# esquema_sensor.net
KiCad netlist of a schematic drawn in EAGLE
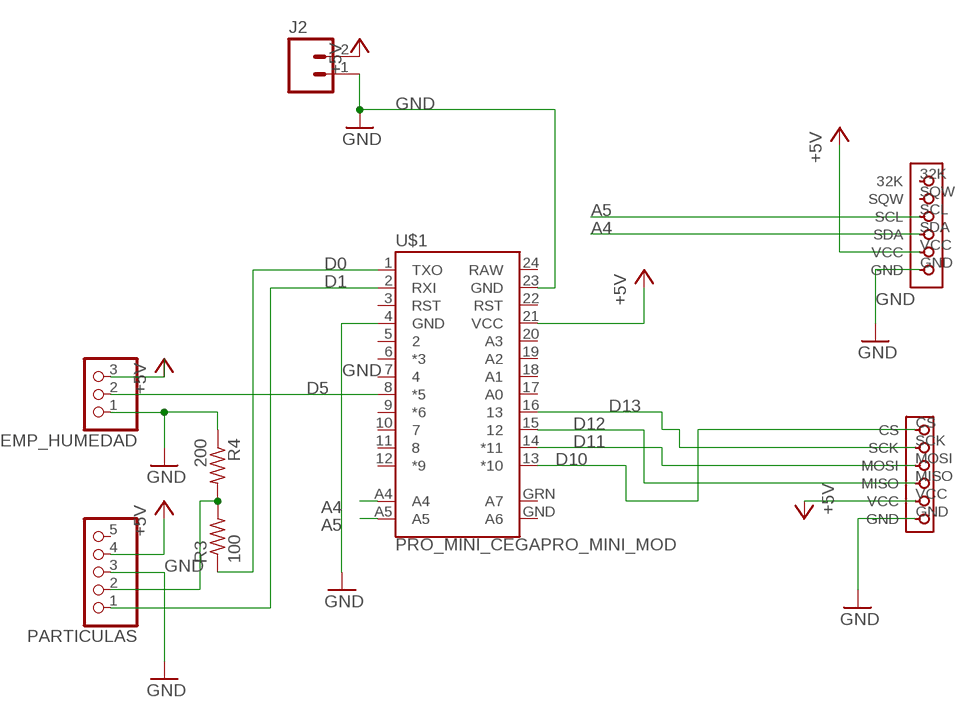
[diagram p0: schematic, sheet 1]

(export (version "E")
  (design (tool "Eeschema 10.0.6"))
  (components
    (comp (ref "J2")
      (value "M025MM")
      (footprint "eagle-import:SCREWTERMINAL-5MM-2")
      (libsource (lib "eagle-import") (part "M025MM"))
    )
    (comp (ref "PARTICULAS")
      (value "PINHD-1X5")
      (footprint "eagle-import:1X05")
      (libsource (lib "eagle-import") (part "PINHD-1X5"))
    )
    (comp (ref "R3")
      (value "100")
      (footprint "eagle-import:0207_7")
      (libsource (lib "eagle-import") (part "R-US_0207/7"))
    )
    (comp (ref "R4")
      (value "200")
      (footprint "eagle-import:0207_7")
      (libsource (lib "eagle-import") (part "R-US_0207/7"))
    )
    (comp (ref "RTC")
      (value "DS3231_RTC")
      (footprint "eagle-import:DS3231_RTC")
      (libsource (lib "eagle-import") (part "DS3231_RTC"))
    )
    (comp (ref "SD_READER")
      (value "MICRO_SD_READER")
      (footprint "eagle-import:MICRO_SD_READER")
      (libsource (lib "eagle-import") (part "MICRO_SD_READER"))
    )
    (comp (ref "TEMP_HUMEDAD")
      (value "PINHD-1X3")
      (footprint "eagle-import:1X03")
      (libsource (lib "eagle-import") (part "PINHD-1X3"))
    )
    (comp (ref "U$1")
      (value "PRO_MINI_CEGAPRO_MINI_MOD")
      (footprint "eagle-import:ARDUINO_PRO_MINI_MOD")
      (libsource (lib "eagle-import") (part "PRO_MINI_CEGAPRO_MINI_MOD"))
    )
  )
  (nets
    (net (code "1") (name "+5V") (class "Default")
      (node (ref "J2") (pin "2") (pinfunction "2_2") (pintype "passive"))
      (node (ref "PARTICULAS") (pin "4") (pinfunction "4_4") (pintype "passive"))
      (node (ref "RTC") (pin "VCC") (pinfunction "VCC_VCC") (pintype "bidirectional"))
      (node (ref "SD_READER") (pin "VCC") (pinfunction "VCC_VCC") (pintype "bidirectional"))
      (node (ref "TEMP_HUMEDAD") (pin "3") (pinfunction "3_3") (pintype "passive"))
      (node (ref "U$1") (pin "21") (pinfunction "VCC_21") (pintype "power_in"))
    )
    (net (code "2") (name "/A4") (class "Default")
      (node (ref "RTC") (pin "SDA") (pinfunction "SDA_SDA") (pintype "bidirectional"))
      (node (ref "U$1") (pin "A4") (pinfunction "A4_A4") (pintype "bidirectional"))
    )
    (net (code "3") (name "/A5") (class "Default")
      (node (ref "RTC") (pin "SCL") (pinfunction "SCL_SCL") (pintype "bidirectional"))
      (node (ref "U$1") (pin "A5") (pinfunction "A5_A5") (pintype "bidirectional"))
    )
    (net (code "4") (name "/D0") (class "Default")
      (node (ref "R3") (pin "1") (pinfunction "1_1") (pintype "passive"))
      (node (ref "U$1") (pin "1") (pinfunction "TXO_1") (pintype "bidirectional"))
    )
    (net (code "5") (name "/D1") (class "Default")
      (node (ref "PARTICULAS") (pin "1") (pinfunction "1_1") (pintype "passive"))
      (node (ref "U$1") (pin "2") (pinfunction "RXI_2") (pintype "bidirectional"))
    )
    (net (code "6") (name "/D5") (class "Default")
      (node (ref "TEMP_HUMEDAD") (pin "2") (pinfunction "2_2") (pintype "passive"))
      (node (ref "U$1") (pin "8") (pinfunction "*5_8") (pintype "bidirectional"))
    )
    (net (code "7") (name "/D10") (class "Default")
      (node (ref "SD_READER") (pin "CS") (pinfunction "CS_CS") (pintype "bidirectional"))
      (node (ref "U$1") (pin "13") (pinfunction "*10_13") (pintype "bidirectional"))
    )
    (net (code "8") (name "/D11") (class "Default")
      (node (ref "SD_READER") (pin "MOSI") (pinfunction "MOSI_MOSI") (pintype "bidirectional"))
      (node (ref "U$1") (pin "14") (pinfunction "*11_14") (pintype "bidirectional"))
    )
    (net (code "9") (name "/D12") (class "Default")
      (node (ref "SD_READER") (pin "MISO") (pinfunction "MISO_MISO") (pintype "bidirectional"))
      (node (ref "U$1") (pin "15") (pinfunction "12_15") (pintype "bidirectional"))
    )
    (net (code "10") (name "/D13") (class "Default")
      (node (ref "SD_READER") (pin "SCK") (pinfunction "SCK_SCK") (pintype "bidirectional"))
      (node (ref "U$1") (pin "16") (pinfunction "13_16") (pintype "bidirectional"))
    )
    (net (code "11") (name "/RAW") (class "Default")
      (node (ref "U$1") (pin "24") (pinfunction "RAW_24") (pintype "power_in"))
    )
    (net (code "12") (name "GND") (class "Default")
      (node (ref "J2") (pin "1") (pinfunction "1_1") (pintype "passive"))
      (node (ref "PARTICULAS") (pin "3") (pinfunction "3_3") (pintype "passive"))
      (node (ref "R4") (pin "1") (pinfunction "1_1") (pintype "passive"))
      (node (ref "RTC") (pin "GND") (pinfunction "GND_GND") (pintype "bidirectional"))
      (node (ref "SD_READER") (pin "GND") (pinfunction "GND_GND") (pintype "bidirectional"))
      (node (ref "TEMP_HUMEDAD") (pin "1") (pinfunction "1_1") (pintype "passive"))
      (node (ref "U$1") (pin "23") (pinfunction "GND_23") (pintype "power_in"))
      (node (ref "U$1") (pin "4") (pinfunction "GND_4") (pintype "power_in"))
    )
    (net (code "13") (name "Net-(PARTICULAS-Pad2)") (class "Default")
      (node (ref "PARTICULAS") (pin "2") (pinfunction "2_2") (pintype "passive"))
      (node (ref "R3") (pin "2") (pinfunction "2_2") (pintype "passive"))
      (node (ref "R4") (pin "2") (pinfunction "2_2") (pintype "passive"))
    )
    (net (code "14") (name "unconnected-(PARTICULAS-Pad5)") (class "Default")
      (node (ref "PARTICULAS") (pin "5") (pinfunction "5_5") (pintype "passive"))
    )
    (net (code "15") (name "unconnected-(RTC-Pad32K)") (class "Default")
      (node (ref "RTC") (pin "32K") (pinfunction "32K_32K") (pintype "bidirectional"))
    )
    (net (code "16") (name "unconnected-(RTC-PadSQW)") (class "Default")
      (node (ref "RTC") (pin "SQW") (pinfunction "SQW_SQW") (pintype "bidirectional"))
    )
    (net (code "17") (name "unconnected-(U$1-*3-Pad6)") (class "Default")
      (node (ref "U$1") (pin "6") (pinfunction "*3_6") (pintype "bidirectional"))
    )
    (net (code "18") (name "unconnected-(U$1-*6-Pad9)") (class "Default")
      (node (ref "U$1") (pin "9") (pinfunction "*6_9") (pintype "bidirectional"))
    )
    (net (code "19") (name "unconnected-(U$1-*9-Pad12)") (class "Default")
      (node (ref "U$1") (pin "12") (pinfunction "*9_12") (pintype "bidirectional"))
    )
    (net (code "20") (name "unconnected-(U$1-2-Pad5)") (class "Default")
      (node (ref "U$1") (pin "5") (pinfunction "2_5") (pintype "bidirectional"))
    )
    (net (code "21") (name "unconnected-(U$1-4-Pad7)") (class "Default")
      (node (ref "U$1") (pin "7") (pinfunction "4_7") (pintype "bidirectional"))
    )
    (net (code "22") (name "unconnected-(U$1-7-Pad10)") (class "Default")
      (node (ref "U$1") (pin "10") (pinfunction "7_10") (pintype "bidirectional"))
    )
    (net (code "23") (name "unconnected-(U$1-8-Pad11)") (class "Default")
      (node (ref "U$1") (pin "11") (pinfunction "8_11") (pintype "bidirectional"))
    )
    (net (code "24") (name "unconnected-(U$1-A0-Pad17)") (class "Default")
      (node (ref "U$1") (pin "17") (pinfunction "A0_17") (pintype "bidirectional"))
    )
    (net (code "25") (name "unconnected-(U$1-A1-Pad18)") (class "Default")
      (node (ref "U$1") (pin "18") (pinfunction "A1_18") (pintype "bidirectional"))
    )
    (net (code "26") (name "unconnected-(U$1-A2-Pad19)") (class "Default")
      (node (ref "U$1") (pin "19") (pinfunction "A2_19") (pintype "bidirectional"))
    )
    (net (code "27") (name "unconnected-(U$1-A3-Pad20)") (class "Default")
      (node (ref "U$1") (pin "20") (pinfunction "A3_20") (pintype "bidirectional"))
    )
    (net (code "28") (name "unconnected-(U$1-A6-PadGND)") (class "Default")
      (node (ref "U$1") (pin "GND") (pinfunction "A6_GND") (pintype "bidirectional"))
    )
    (net (code "29") (name "unconnected-(U$1-A7-PadGRN)") (class "Default")
      (node (ref "U$1") (pin "GRN") (pinfunction "A7_GRN") (pintype "bidirectional"))
    )
    (net (code "30") (name "unconnected-(U$1-RST-Pad3)") (class "Default")
      (node (ref "U$1") (pin "3") (pinfunction "RST_3") (pintype "bidirectional"))
    )
    (net (code "31") (name "unconnected-(U$1-RST-Pad22)") (class "Default")
      (node (ref "U$1") (pin "22") (pinfunction "RST_22") (pintype "bidirectional"))
    )
  )
)
